# SCH_towed-rov_2022-04-12.net
KiCad netlist of a schematic drawn in EasyEDA
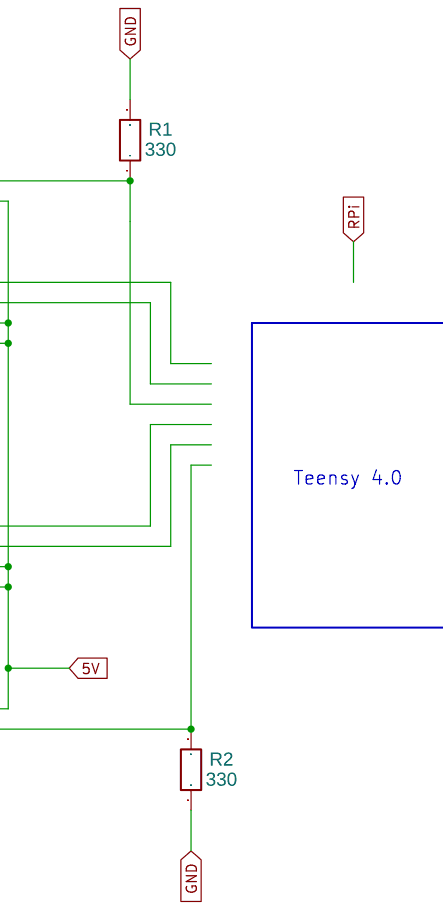
[diagram p0: schematic sheet]

(export (version "E")
  (design (tool "Eeschema 10.0.6"))
  (components
    (comp (ref "R1") (value "330") (libsource (lib "") (part "R_0603_EU")))
    (comp (ref "R2") (value "330") (libsource (lib "") (part "R_0603_EU")))
  )
  (nets
    (net (code "3") (name "GND") (class "Default")
      (node (ref "R1") (pin "2") (pinfunction "2_2") (pintype "unspecified"))
      (node (ref "R2") (pin "1") (pinfunction "1_1") (pintype "unspecified"))
    )
    (net (code "5") (name "unconnected-(R1-Pad1)") (class "Default")
      (node (ref "R1") (pin "1") (pinfunction "1_1") (pintype "unspecified"))
    )
    (net (code "6") (name "unconnected-(R2-Pad2)") (class "Default")
      (node (ref "R2") (pin "2") (pinfunction "2_2") (pintype "unspecified"))
    )
  )
)
